# Adafruit_FT232H.net
KiCad netlist of a schematic drawn in EAGLE
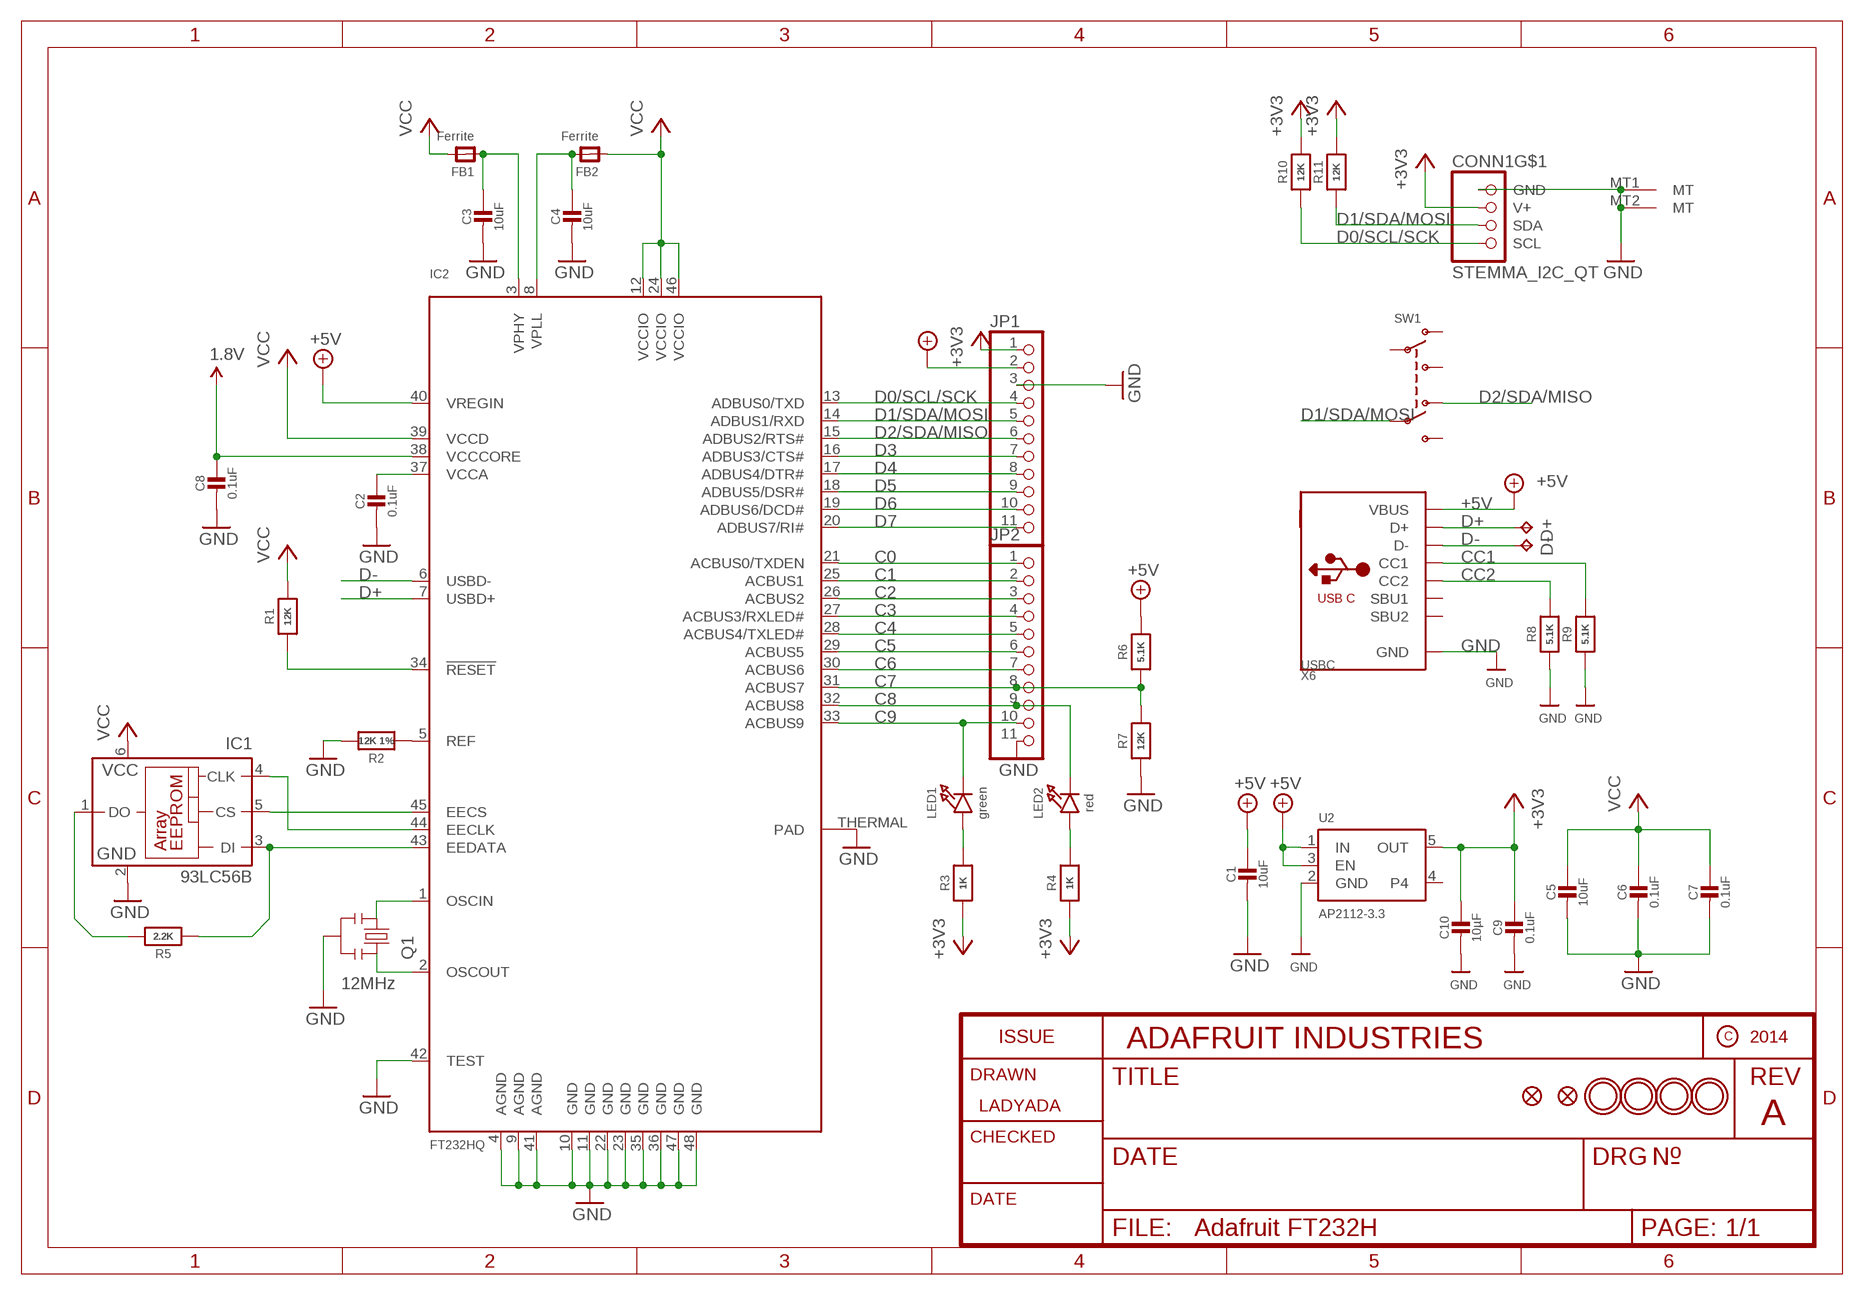
[diagram p0: schematic, sheet 1]

(export (version "E")
  (design (tool "Eeschema 10.0.6"))
  (components
    (comp (ref "C1")
      (value "10uF")
      (footprint "eagle-import:0805-NO")
      (libsource (lib "eagle-import") (part "CAP_CERAMIC0805-NOOUTLINE"))
    )
    (comp (ref "C2")
      (value "0.1uF")
      (footprint "eagle-import:0603-NO")
      (libsource (lib "eagle-import") (part "CAP_CERAMIC0603_NO"))
    )
    (comp (ref "C3")
      (value "10uF")
      (footprint "eagle-import:0805-NO")
      (libsource (lib "eagle-import") (part "CAP_CERAMIC0805-NOOUTLINE"))
    )
    (comp (ref "C4")
      (value "10uF")
      (footprint "eagle-import:0805-NO")
      (libsource (lib "eagle-import") (part "CAP_CERAMIC0805-NOOUTLINE"))
    )
    (comp (ref "C5")
      (value "10uF")
      (footprint "eagle-import:0805-NO")
      (libsource (lib "eagle-import") (part "CAP_CERAMIC0805-NOOUTLINE"))
    )
    (comp (ref "C6")
      (value "0.1uF")
      (footprint "eagle-import:0603-NO")
      (libsource (lib "eagle-import") (part "CAP_CERAMIC0603_NO"))
    )
    (comp (ref "C7")
      (value "0.1uF")
      (footprint "eagle-import:0603-NO")
      (libsource (lib "eagle-import") (part "CAP_CERAMIC0603_NO"))
    )
    (comp (ref "C8")
      (value "0.1uF")
      (footprint "eagle-import:0603-NO")
      (libsource (lib "eagle-import") (part "CAP_CERAMIC0603_NO"))
    )
    (comp (ref "C9")
      (value "0.1uF")
      (footprint "eagle-import:0603-NO")
      (libsource (lib "eagle-import") (part "CAP_CERAMIC0603_NO"))
    )
    (comp (ref "C10")
      (value "10µF")
      (footprint "eagle-import:0805-NO")
      (fields (field (name "REV") "A"))
      (libsource (lib "eagle-import") (part "CAP_CERAMIC0805-NOOUTLINE"))
    )
    (comp (ref "CONN1")
      (value "STEMMA_I2C_QT")
      (footprint "eagle-import:JST_SH4")
      (libsource (lib "eagle-import") (part "STEMMA_I2C_QT"))
    )
    (comp (ref "D+")
      (value "TPTP17R")
      (footprint "eagle-import:TP17R")
      (libsource (lib "eagle-import") (part "TPTP17R"))
    )
    (comp (ref "D-")
      (value "TPTP17R")
      (footprint "eagle-import:TP17R")
      (libsource (lib "eagle-import") (part "TPTP17R"))
    )
    (comp (ref "FB1")
      (value "Ferrite")
      (footprint "eagle-import:_0805")
      (libsource (lib "eagle-import") (part "FERRITE_0805"))
    )
    (comp (ref "FB2")
      (value "Ferrite")
      (footprint "eagle-import:_0805")
      (libsource (lib "eagle-import") (part "FERRITE_0805"))
    )
    (comp (ref "FID1")
      (value "FIDUCIAL\"\"")
      (footprint "eagle-import:FIDUCIAL_1MM")
      (libsource (lib "eagle-import") (part "FIDUCIAL{dblquote}{dblquote}"))
    )
    (comp (ref "FID2")
      (value "FIDUCIAL\"\"")
      (footprint "eagle-import:FIDUCIAL_1MM")
      (libsource (lib "eagle-import") (part "FIDUCIAL{dblquote}{dblquote}"))
    )
    (comp (ref "IC1")
      (value "93LC56B")
      (footprint "eagle-import:SOT23-6")
      (fields (field (name "MF") "MICROCHIP") (field (name "MPN") "93LC76AT-I/OT"))
      (libsource (lib "eagle-import") (part "9376?ALC"))
    )
    (comp (ref "IC2")
      (value "FT232HQ")
      (footprint "eagle-import:QFN48_8MM")
      (libsource (lib "eagle-import") (part "FT232HQ"))
    )
    (comp (ref "JP1")
      (value "HEADER-1X11")
      (footprint "eagle-import:1X11_ROUND")
      (libsource (lib "eagle-import") (part "HEADER-1X11"))
    )
    (comp (ref "JP2")
      (value "HEADER-1X11")
      (footprint "eagle-import:1X11_ROUND")
      (libsource (lib "eagle-import") (part "HEADER-1X11"))
    )
    (comp (ref "LED1")
      (value "green")
      (footprint "eagle-import:CHIPLED_0805_NOOUTLINE")
      (libsource (lib "eagle-import") (part "LED0805_NOOUTLINE"))
    )
    (comp (ref "LED2")
      (value "red")
      (footprint "eagle-import:CHIPLED_0805_NOOUTLINE")
      (libsource (lib "eagle-import") (part "LED0805_NOOUTLINE"))
    )
    (comp (ref "Q1")
      (value "12MHz")
      (footprint "eagle-import:RESONATOR-SMD")
      (libsource (lib "eagle-import") (part "RESONATORSMD"))
    )
    (comp (ref "R1")
      (value "12K")
      (footprint "eagle-import:0603-NO")
      (libsource (lib "eagle-import") (part "RESISTOR_0603_NOOUT"))
    )
    (comp (ref "R2")
      (value "12K 1%")
      (footprint "eagle-import:0603-NO")
      (libsource (lib "eagle-import") (part "RESISTOR_0603_NOOUT"))
    )
    (comp (ref "R3")
      (value "1K")
      (footprint "eagle-import:0603-NO")
      (libsource (lib "eagle-import") (part "RESISTOR_0603_NOOUT"))
    )
    (comp (ref "R4")
      (value "1K")
      (footprint "eagle-import:0603-NO")
      (libsource (lib "eagle-import") (part "RESISTOR_0603_NOOUT"))
    )
    (comp (ref "R5")
      (value "2.2K")
      (footprint "eagle-import:0603-NO")
      (libsource (lib "eagle-import") (part "RESISTOR_0603_NOOUT"))
    )
    (comp (ref "R6")
      (value "5.1K")
      (footprint "eagle-import:0603-NO")
      (libsource (lib "eagle-import") (part "RESISTOR_0603_NOOUT"))
    )
    (comp (ref "R7")
      (value "12K")
      (footprint "eagle-import:0603-NO")
      (libsource (lib "eagle-import") (part "RESISTOR_0603_NOOUT"))
    )
    (comp (ref "R8")
      (value "5.1K")
      (footprint "eagle-import:0603-NO")
      (libsource (lib "eagle-import") (part "RESISTOR_0603_NOOUT"))
    )
    (comp (ref "R9")
      (value "5.1K")
      (footprint "eagle-import:0603-NO")
      (libsource (lib "eagle-import") (part "RESISTOR_0603_NOOUT"))
    )
    (comp (ref "R10")
      (value "12K")
      (footprint "eagle-import:0603-NO")
      (libsource (lib "eagle-import") (part "RESISTOR_0603_NOOUT"))
    )
    (comp (ref "R11")
      (value "12K")
      (footprint "eagle-import:0603-NO")
      (libsource (lib "eagle-import") (part "RESISTOR_0603_NOOUT"))
    )
    (comp (ref "SW1")
      (value "SWITCH_DPDTEG1390")
      (footprint "eagle-import:EG1390")
      (libsource (lib "eagle-import") (part "SWITCH_DPDTEG1390"))
    )
    (comp (ref "U$4")
      (value "MOUNTINGHOLE2.5")
      (footprint "eagle-import:MOUNTINGHOLE_2.5_PLATED")
      (libsource (lib "eagle-import") (part "MOUNTINGHOLE2.5"))
    )
    (comp (ref "U$5")
      (value "MOUNTINGHOLE2.5")
      (footprint "eagle-import:MOUNTINGHOLE_2.5_PLATED")
      (libsource (lib "eagle-import") (part "MOUNTINGHOLE2.5"))
    )
    (comp (ref "U$6")
      (value "MOUNTINGHOLE2.5")
      (footprint "eagle-import:MOUNTINGHOLE_2.5_PLATED")
      (fields (field (name "BOM") "EXCLUDE") (field (name "REV") "D"))
      (libsource (lib "eagle-import") (part "MOUNTINGHOLE2.5"))
    )
    (comp (ref "U$7")
      (value "MOUNTINGHOLE2.5")
      (footprint "eagle-import:MOUNTINGHOLE_2.5_PLATED")
      (libsource (lib "eagle-import") (part "MOUNTINGHOLE2.5"))
    )
    (comp (ref "U2")
      (value "AP2112-3.3")
      (footprint "eagle-import:SOT23-5")
      (libsource (lib "eagle-import") (part "VREG_SOT23-5"))
    )
    (comp (ref "X6")
      (value "USBC")
      (footprint "eagle-import:USB_C_CUSB31-CFM2AX-01-X")
      (libsource (lib "eagle-import") (part "USB_C"))
    )
  )
  (nets
    (net (code "1") (name "+3V3") (class "Default")
      (node (ref "C10") (pin "1") (pinfunction "1_1") (pintype "passive"))
      (node (ref "C9") (pin "1") (pinfunction "1_1") (pintype "passive"))
      (node (ref "CONN1") (pin "2") (pinfunction "V+_2") (pintype "passive"))
      (node (ref "JP1") (pin "1") (pinfunction "1_1") (pintype "passive"))
      (node (ref "R10") (pin "2") (pinfunction "2_2") (pintype "passive"))
      (node (ref "R11") (pin "2") (pinfunction "2_2") (pintype "passive"))
      (node (ref "R3") (pin "1") (pinfunction "1_1") (pintype "passive"))
      (node (ref "R4") (pin "1") (pinfunction "1_1") (pintype "passive"))
      (node (ref "U2") (pin "5") (pinfunction "OUT_5") (pintype "power_in"))
    )
    (net (code "2") (name "+5V") (class "Default")
      (node (ref "C1") (pin "1") (pinfunction "1_1") (pintype "passive"))
      (node (ref "IC2") (pin "40") (pinfunction "VREGIN_40") (pintype "power_in"))
      (node (ref "JP1") (pin "2") (pinfunction "2_2") (pintype "passive"))
      (node (ref "R6") (pin "2") (pinfunction "2_2") (pintype "passive"))
      (node (ref "U2") (pin "1") (pinfunction "IN_1") (pintype "power_in"))
      (node (ref "U2") (pin "3") (pinfunction "EN_3") (pintype "input"))
      (node (ref "X6") (pin "A4B9") (pinfunction "VBUS_A4B9") (pintype "power_in"))
      (node (ref "X6") (pin "B4A9") (pinfunction "VBUS_B4A9") (pintype "power_in"))
    )
    (net (code "3") (name "/C0") (class "Default")
      (node (ref "IC2") (pin "21") (pinfunction "ACBUS0/TXDEN_21") (pintype "bidirectional"))
      (node (ref "JP2") (pin "1") (pinfunction "1_1") (pintype "passive"))
    )
    (net (code "4") (name "/C1") (class "Default")
      (node (ref "IC2") (pin "25") (pinfunction "ACBUS1_25") (pintype "bidirectional"))
      (node (ref "JP2") (pin "2") (pinfunction "2_2") (pintype "passive"))
    )
    (net (code "5") (name "/C2") (class "Default")
      (node (ref "IC2") (pin "26") (pinfunction "ACBUS2_26") (pintype "bidirectional"))
      (node (ref "JP2") (pin "3") (pinfunction "3_3") (pintype "passive"))
    )
    (net (code "6") (name "/C3") (class "Default")
      (node (ref "IC2") (pin "27") (pinfunction "ACBUS3/RXLED#_27") (pintype "bidirectional"))
      (node (ref "JP2") (pin "4") (pinfunction "4_4") (pintype "passive"))
    )
    (net (code "7") (name "/C4") (class "Default")
      (node (ref "IC2") (pin "28") (pinfunction "ACBUS4/TXLED#_28") (pintype "bidirectional"))
      (node (ref "JP2") (pin "5") (pinfunction "5_5") (pintype "passive"))
    )
    (net (code "8") (name "/C5") (class "Default")
      (node (ref "IC2") (pin "29") (pinfunction "ACBUS5_29") (pintype "bidirectional"))
      (node (ref "JP2") (pin "6") (pinfunction "6_6") (pintype "passive"))
    )
    (net (code "9") (name "/C6") (class "Default")
      (node (ref "IC2") (pin "30") (pinfunction "ACBUS6_30") (pintype "bidirectional"))
      (node (ref "JP2") (pin "7") (pinfunction "7_7") (pintype "passive"))
    )
    (net (code "10") (name "/C7") (class "Default")
      (node (ref "IC2") (pin "31") (pinfunction "ACBUS7_31") (pintype "bidirectional"))
      (node (ref "JP2") (pin "8") (pinfunction "8_8") (pintype "passive"))
      (node (ref "R6") (pin "1") (pinfunction "1_1") (pintype "passive"))
      (node (ref "R7") (pin "2") (pinfunction "2_2") (pintype "passive"))
    )
    (net (code "11") (name "/C8") (class "Default")
      (node (ref "IC2") (pin "32") (pinfunction "ACBUS8_32") (pintype "bidirectional"))
      (node (ref "JP2") (pin "9") (pinfunction "9_9") (pintype "passive"))
      (node (ref "LED2") (pin "C") (pinfunction "C_C") (pintype "passive"))
    )
    (net (code "12") (name "/C9") (class "Default")
      (node (ref "IC2") (pin "33") (pinfunction "ACBUS9_33") (pintype "bidirectional"))
      (node (ref "JP2") (pin "10") (pinfunction "10_10") (pintype "passive"))
      (node (ref "LED1") (pin "C") (pinfunction "C_C") (pintype "passive"))
    )
    (net (code "13") (name "/CC1") (class "Default")
      (node (ref "R9") (pin "2") (pinfunction "2_2") (pintype "passive"))
      (node (ref "X6") (pin "A5") (pinfunction "CC1_A5") (pintype "bidirectional"))
    )
    (net (code "14") (name "/CC2") (class "Default")
      (node (ref "R8") (pin "2") (pinfunction "2_2") (pintype "passive"))
      (node (ref "X6") (pin "B5") (pinfunction "CC2_B5") (pintype "bidirectional"))
    )
    (net (code "15") (name "/D+") (class "Default")
      (node (ref "D+") (pin "TP") (pinfunction "TP_TP") (pintype "input"))
      (node (ref "IC2") (pin "7") (pinfunction "USBD+_7") (pintype "bidirectional"))
      (node (ref "X6") (pin "A6") (pinfunction "D+_A6") (pintype "bidirectional"))
      (node (ref "X6") (pin "B6") (pinfunction "D+_B6") (pintype "bidirectional"))
    )
    (net (code "16") (name "/D-") (class "Default")
      (node (ref "D-") (pin "TP") (pinfunction "TP_TP") (pintype "input"))
      (node (ref "IC2") (pin "6") (pinfunction "USBD-_6") (pintype "bidirectional"))
      (node (ref "X6") (pin "A7") (pinfunction "D-_A7") (pintype "bidirectional"))
      (node (ref "X6") (pin "B7") (pinfunction "D-_B7") (pintype "bidirectional"))
    )
    (net (code "17") (name "/D0{slash}SCL{slash}SCK") (class "Default")
      (node (ref "CONN1") (pin "4") (pinfunction "SCL_4") (pintype "passive"))
      (node (ref "IC2") (pin "13") (pinfunction "ADBUS0/TXD_13") (pintype "output"))
      (node (ref "JP1") (pin "4") (pinfunction "4_4") (pintype "passive"))
      (node (ref "R10") (pin "1") (pinfunction "1_1") (pintype "passive"))
    )
    (net (code "18") (name "/D1{slash}SDA{slash}MOSI") (class "Default")
      (node (ref "CONN1") (pin "3") (pinfunction "SDA_3") (pintype "passive"))
      (node (ref "IC2") (pin "14") (pinfunction "ADBUS1/RXD_14") (pintype "input"))
      (node (ref "JP1") (pin "5") (pinfunction "5_5") (pintype "passive"))
      (node (ref "R11") (pin "1") (pinfunction "1_1") (pintype "passive"))
      (node (ref "SW1") (pin "P2") (pinfunction "P2_P2") (pintype "passive"))
    )
    (net (code "19") (name "/D2{slash}SDA{slash}MISO") (class "Default")
      (node (ref "IC2") (pin "15") (pinfunction "ADBUS2/RTS#_15") (pintype "output"))
      (node (ref "JP1") (pin "6") (pinfunction "6_6") (pintype "passive"))
      (node (ref "SW1") (pin "O2") (pinfunction "O2_O2") (pintype "passive"))
    )
    (net (code "20") (name "/D3") (class "Default")
      (node (ref "IC2") (pin "16") (pinfunction "ADBUS3/CTS#_16") (pintype "input"))
      (node (ref "JP1") (pin "7") (pinfunction "7_7") (pintype "passive"))
    )
    (net (code "21") (name "/D4") (class "Default")
      (node (ref "IC2") (pin "17") (pinfunction "ADBUS4/DTR#_17") (pintype "output"))
      (node (ref "JP1") (pin "8") (pinfunction "8_8") (pintype "passive"))
    )
    (net (code "22") (name "/D5") (class "Default")
      (node (ref "IC2") (pin "18") (pinfunction "ADBUS5/DSR#_18") (pintype "input"))
      (node (ref "JP1") (pin "9") (pinfunction "9_9") (pintype "passive"))
    )
    (net (code "23") (name "/D6") (class "Default")
      (node (ref "IC2") (pin "19") (pinfunction "ADBUS6/DCD#_19") (pintype "input"))
      (node (ref "JP1") (pin "10") (pinfunction "10_10") (pintype "passive"))
    )
    (net (code "24") (name "/D7") (class "Default")
      (node (ref "IC2") (pin "20") (pinfunction "ADBUS7/RI#_20") (pintype "input"))
      (node (ref "JP1") (pin "11") (pinfunction "11_11") (pintype "passive"))
    )
    (net (code "25") (name "1.8V") (class "Default")
      (node (ref "C8") (pin "1") (pinfunction "1_1") (pintype "passive"))
      (node (ref "IC2") (pin "38") (pinfunction "VCCCORE_38") (pintype "power_in"))
    )
    (net (code "26") (name "GND") (class "Default")
      (node (ref "C1") (pin "2") (pinfunction "2_2") (pintype "passive"))
      (node (ref "C10") (pin "2") (pinfunction "2_2") (pintype "passive"))
      (node (ref "C2") (pin "2") (pinfunction "2_2") (pintype "passive"))
      (node (ref "C3") (pin "2") (pinfunction "2_2") (pintype "passive"))
      (node (ref "C4") (pin "2") (pinfunction "2_2") (pintype "passive"))
      (node (ref "C5") (pin "2") (pinfunction "2_2") (pintype "passive"))
      (node (ref "C6") (pin "2") (pinfunction "2_2") (pintype "passive"))
      (node (ref "C7") (pin "2") (pinfunction "2_2") (pintype "passive"))
      (node (ref "C8") (pin "2") (pinfunction "2_2") (pintype "passive"))
      (node (ref "C9") (pin "2") (pinfunction "2_2") (pintype "passive"))
      (node (ref "CONN1") (pin "1") (pinfunction "GND_1") (pintype "passive"))
      (node (ref "CONN1") (pin "MT1") (pinfunction "MT_MT1") (pintype "bidirectional"))
      (node (ref "CONN1") (pin "MT2") (pinfunction "MT_MT2") (pintype "bidirectional"))
      (node (ref "IC1") (pin "2") (pinfunction "GND_2") (pintype "power_in"))
      (node (ref "IC2") (pin "10") (pinfunction "GND_10") (pintype "power_in"))
      (node (ref "IC2") (pin "11") (pinfunction "GND_11") (pintype "power_in"))
      (node (ref "IC2") (pin "22") (pinfunction "GND_22") (pintype "power_in"))
      (node (ref "IC2") (pin "23") (pinfunction "GND_23") (pintype "power_in"))
      (node (ref "IC2") (pin "35") (pinfunction "GND_35") (pintype "power_in"))
      (node (ref "IC2") (pin "36") (pinfunction "GND_36") (pintype "power_in"))
      (node (ref "IC2") (pin "4") (pinfunction "AGND_4") (pintype "power_in"))
      (node (ref "IC2") (pin "41") (pinfunction "AGND_41") (pintype "power_in"))
      (node (ref "IC2") (pin "42") (pinfunction "TEST_42") (pintype "input"))
      (node (ref "IC2") (pin "47") (pinfunction "GND_47") (pintype "power_in"))
      (node (ref "IC2") (pin "48") (pinfunction "GND_48") (pintype "power_in"))
      (node (ref "IC2") (pin "9") (pinfunction "AGND_9") (pintype "power_in"))
      (node (ref "IC2") (pin "THERMAL") (pinfunction "PAD_THERMAL") (pintype "passive"))
      (node (ref "JP1") (pin "3") (pinfunction "3_3") (pintype "passive"))
      (node (ref "JP2") (pin "11") (pinfunction "11_11") (pintype "passive"))
      (node (ref "Q1") (pin "2") (pinfunction "2_2") (pintype "passive"))
      (node (ref "R2") (pin "2") (pinfunction "2_2") (pintype "passive"))
      (node (ref "R7") (pin "1") (pinfunction "1_1") (pintype "passive"))
      (node (ref "R8") (pin "1") (pinfunction "1_1") (pintype "passive"))
      (node (ref "R9") (pin "1") (pinfunction "1_1") (pintype "passive"))
      (node (ref "U2") (pin "2") (pinfunction "GND_2") (pintype "power_in"))
      (node (ref "X6") (pin "A1B12") (pinfunction "GND_A1B12") (pintype "power_in"))
      (node (ref "X6") (pin "B1A12") (pinfunction "GND_B1A12") (pintype "power_in"))
    )
    (net (code "27") (name "Net-(FB1-P$1)") (class "Default")
      (node (ref "C3") (pin "1") (pinfunction "1_1") (pintype "passive"))
      (node (ref "FB1") (pin "1") (pinfunction "P$1_1") (pintype "passive"))
      (node (ref "IC2") (pin "3") (pinfunction "VPHY_3") (pintype "power_in"))
    )
    (net (code "28") (name "Net-(FB2-P$2)") (class "Default")
      (node (ref "C4") (pin "1") (pinfunction "1_1") (pintype "passive"))
      (node (ref "FB2") (pin "2") (pinfunction "P$2_2") (pintype "passive"))
      (node (ref "IC2") (pin "8") (pinfunction "VPLL_8") (pintype "power_in"))
    )
    (net (code "29") (name "Net-(IC1-CLK)") (class "Default")
      (node (ref "IC1") (pin "4") (pinfunction "CLK_4") (pintype "input"))
      (node (ref "IC2") (pin "44") (pinfunction "EECLK_44") (pintype "output"))
    )
    (net (code "30") (name "Net-(IC1-CS)") (class "Default")
      (node (ref "IC1") (pin "5") (pinfunction "CS_5") (pintype "input"))
      (node (ref "IC2") (pin "45") (pinfunction "EECS_45") (pintype "bidirectional"))
    )
    (net (code "31") (name "Net-(IC1-DI)") (class "Default")
      (node (ref "IC1") (pin "3") (pinfunction "DI_3") (pintype "input"))
      (node (ref "IC2") (pin "43") (pinfunction "EEDATA_43") (pintype "bidirectional"))
      (node (ref "R5") (pin "1") (pinfunction "1_1") (pintype "passive"))
    )
    (net (code "32") (name "Net-(IC1-DO)") (class "Default")
      (node (ref "IC1") (pin "1") (pinfunction "DO_1") (pintype "tri_state"))
      (node (ref "R5") (pin "2") (pinfunction "2_2") (pintype "passive"))
    )
    (net (code "33") (name "Net-(IC2-OSCIN)") (class "Default")
      (node (ref "IC2") (pin "1") (pinfunction "OSCIN_1") (pintype "input"))
      (node (ref "Q1") (pin "1") (pinfunction "1_1") (pintype "passive"))
    )
    (net (code "34") (name "Net-(IC2-OSCOUT)") (class "Default")
      (node (ref "IC2") (pin "2") (pinfunction "OSCOUT_2") (pintype "output"))
      (node (ref "Q1") (pin "3") (pinfunction "3_3") (pintype "passive"))
    )
    (net (code "35") (name "Net-(IC2-REF)") (class "Default")
      (node (ref "IC2") (pin "5") (pinfunction "REF_5") (pintype "input"))
      (node (ref "R2") (pin "1") (pinfunction "1_1") (pintype "passive"))
    )
    (net (code "36") (name "Net-(IC2-VCCA)") (class "Default")
      (node (ref "C2") (pin "1") (pinfunction "1_1") (pintype "passive"))
      (node (ref "IC2") (pin "37") (pinfunction "VCCA_37") (pintype "power_in"))
    )
    (net (code "37") (name "Net-(IC2-~{RESET})") (class "Default")
      (node (ref "IC2") (pin "34") (pinfunction "~{RESET}_34") (pintype "input"))
      (node (ref "R1") (pin "1") (pinfunction "1_1") (pintype "passive"))
    )
    (net (code "38") (name "Net-(LED1-PadA)") (class "Default")
      (node (ref "LED1") (pin "A") (pinfunction "A_A") (pintype "passive"))
      (node (ref "R3") (pin "2") (pinfunction "2_2") (pintype "passive"))
    )
    (net (code "39") (name "Net-(LED2-PadA)") (class "Default")
      (node (ref "LED2") (pin "A") (pinfunction "A_A") (pintype "passive"))
      (node (ref "R4") (pin "2") (pinfunction "2_2") (pintype "passive"))
    )
    (net (code "40") (name "VCC") (class "Default")
      (node (ref "C5") (pin "1") (pinfunction "1_1") (pintype "passive"))
      (node (ref "C6") (pin "1") (pinfunction "1_1") (pintype "passive"))
      (node (ref "C7") (pin "1") (pinfunction "1_1") (pintype "passive"))
      (node (ref "FB1") (pin "2") (pinfunction "P$2_2") (pintype "passive"))
      (node (ref "FB2") (pin "1") (pinfunction "P$1_1") (pintype "passive"))
      (node (ref "IC1") (pin "6") (pinfunction "VCC_6") (pintype "power_in"))
      (node (ref "IC2") (pin "12") (pinfunction "VCCIO_12") (pintype "power_in"))
      (node (ref "IC2") (pin "24") (pinfunction "VCCIO_24") (pintype "power_in"))
      (node (ref "IC2") (pin "39") (pinfunction "VCCD_39") (pintype "power_in"))
      (node (ref "IC2") (pin "46") (pinfunction "VCCIO_46") (pintype "power_in"))
      (node (ref "R1") (pin "2") (pinfunction "2_2") (pintype "passive"))
    )
    (net (code "41") (name "unconnected-(SW1-PadO1)") (class "Default")
      (node (ref "SW1") (pin "O1") (pinfunction "O1_O1") (pintype "passive"))
    )
    (net (code "42") (name "unconnected-(SW1-PadP1)") (class "Default")
      (node (ref "SW1") (pin "P1") (pinfunction "P1_P1") (pintype "passive"))
    )
    (net (code "43") (name "unconnected-(SW1-PadS1)") (class "Default")
      (node (ref "SW1") (pin "S1") (pinfunction "S1_S1") (pintype "passive"))
    )
    (net (code "44") (name "unconnected-(SW1-PadS2)") (class "Default")
      (node (ref "SW1") (pin "S2") (pinfunction "S2_S2") (pintype "passive"))
    )
    (net (code "45") (name "unconnected-(U2-P4-Pad4)") (class "Default")
      (node (ref "U2") (pin "4") (pinfunction "P4_4") (pintype "bidirectional"))
    )
    (net (code "46") (name "unconnected-(X6-SBU1-PadA8)") (class "Default")
      (node (ref "X6") (pin "A8") (pinfunction "SBU1_A8") (pintype "bidirectional"))
    )
    (net (code "47") (name "unconnected-(X6-SBU2-PadB8)") (class "Default")
      (node (ref "X6") (pin "B8") (pinfunction "SBU2_B8") (pintype "bidirectional"))
    )
  )
)
